# Circuito_el_trico.net
KiCad netlist of a schematic drawn in EAGLE
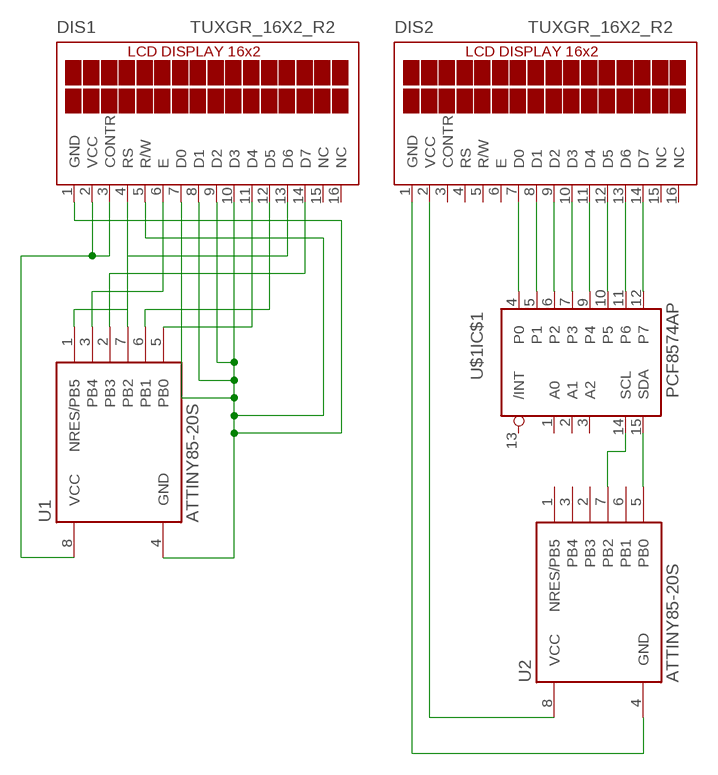
[diagram p0: schematic, sheet 1]

(export (version "E")
  (design (tool "Eeschema 10.0.6"))
  (components
    (comp (ref "DIS1")
      (value "TUXGR_16X2_R2")
      (footprint "eagle-import:TUXGR_16X2_R2")
      (libsource (lib "eagle-import") (part "TUXGR_16X2_R2"))
    )
    (comp (ref "DIS2")
      (value "TUXGR_16X2_R2")
      (footprint "eagle-import:TUXGR_16X2_R2")
      (libsource (lib "eagle-import") (part "TUXGR_16X2_R2"))
    )
    (comp (ref "U$1")
      (value "PCF8574AP")
      (footprint "eagle-import:DIL16")
      (libsource (lib "eagle-import") (part "PCF8574AP"))
    )
    (comp (ref "U1")
      (value "ATTINY85-20S")
      (footprint "eagle-import:SOIC8_EIAJ_208MIL")
      (libsource (lib "eagle-import") (part "ATTINY85S-20"))
    )
    (comp (ref "U2")
      (value "ATTINY85-20S")
      (footprint "eagle-import:SOIC8_EIAJ_208MIL")
      (libsource (lib "eagle-import") (part "ATTINY85S-20"))
    )
  )
  (nets
    (net (code "1") (name "Net-(DIS1-CONTR)") (class "Default")
      (node (ref "DIS1") (pin "2") (pinfunction "VCC_2") (pintype "power_in"))
      (node (ref "DIS1") (pin "3") (pinfunction "CONTR_3") (pintype "input"))
      (node (ref "U1") (pin "8") (pinfunction "VCC_8") (pintype "power_in"))
    )
    (net (code "2") (name "Net-(DIS1-D0)") (class "Default")
      (node (ref "DIS1") (pin "1") (pinfunction "GND_1") (pintype "power_in"))
      (node (ref "DIS1") (pin "10") (pinfunction "D3_10") (pintype "input"))
      (node (ref "DIS1") (pin "5") (pinfunction "R/W_5") (pintype "input"))
      (node (ref "DIS1") (pin "7") (pinfunction "D0_7") (pintype "input"))
      (node (ref "DIS1") (pin "8") (pinfunction "D1_8") (pintype "input"))
      (node (ref "DIS1") (pin "9") (pinfunction "D2_9") (pintype "input"))
      (node (ref "U1") (pin "4") (pinfunction "GND_4") (pintype "power_in"))
    )
    (net (code "3") (name "Net-(DIS1-D4)") (class "Default")
      (node (ref "DIS1") (pin "11") (pinfunction "D4_11") (pintype "input"))
      (node (ref "U1") (pin "5") (pinfunction "PB0_5") (pintype "bidirectional"))
    )
    (net (code "4") (name "Net-(DIS1-D5)") (class "Default")
      (node (ref "DIS1") (pin "12") (pinfunction "D5_12") (pintype "input"))
      (node (ref "U1") (pin "6") (pinfunction "PB1_6") (pintype "bidirectional"))
    )
    (net (code "5") (name "Net-(DIS1-D6)") (class "Default")
      (node (ref "DIS1") (pin "13") (pinfunction "D6_13") (pintype "input"))
      (node (ref "U1") (pin "7") (pinfunction "PB2_7") (pintype "bidirectional"))
    )
    (net (code "6") (name "Net-(DIS1-D7)") (class "Default")
      (node (ref "DIS1") (pin "14") (pinfunction "D7_14") (pintype "input"))
      (node (ref "U1") (pin "2") (pinfunction "PB3_2") (pintype "bidirectional"))
    )
    (net (code "7") (name "Net-(DIS1-E)") (class "Default")
      (node (ref "DIS1") (pin "6") (pinfunction "E_6") (pintype "input"))
      (node (ref "U1") (pin "3") (pinfunction "PB4_3") (pintype "bidirectional"))
    )
    (net (code "8") (name "Net-(DIS1-RS)") (class "Default")
      (node (ref "DIS1") (pin "4") (pinfunction "RS_4") (pintype "input"))
      (node (ref "U1") (pin "1") (pinfunction "NRES/PB5_1") (pintype "bidirectional"))
    )
    (net (code "9") (name "Net-(DIS2-D0)") (class "Default")
      (node (ref "DIS2") (pin "7") (pinfunction "D0_7") (pintype "input"))
      (node (ref "U$1") (pin "4") (pinfunction "P0_4") (pintype "bidirectional"))
    )
    (net (code "10") (name "Net-(DIS2-D1)") (class "Default")
      (node (ref "DIS2") (pin "8") (pinfunction "D1_8") (pintype "input"))
      (node (ref "U$1") (pin "5") (pinfunction "P1_5") (pintype "bidirectional"))
    )
    (net (code "11") (name "Net-(DIS2-D2)") (class "Default")
      (node (ref "DIS2") (pin "9") (pinfunction "D2_9") (pintype "input"))
      (node (ref "U$1") (pin "6") (pinfunction "P2_6") (pintype "bidirectional"))
    )
    (net (code "12") (name "Net-(DIS2-D3)") (class "Default")
      (node (ref "DIS2") (pin "10") (pinfunction "D3_10") (pintype "input"))
      (node (ref "U$1") (pin "7") (pinfunction "P3_7") (pintype "bidirectional"))
    )
    (net (code "13") (name "Net-(DIS2-D4)") (class "Default")
      (node (ref "DIS2") (pin "11") (pinfunction "D4_11") (pintype "input"))
      (node (ref "U$1") (pin "9") (pinfunction "P4_9") (pintype "bidirectional"))
    )
    (net (code "14") (name "Net-(DIS2-D5)") (class "Default")
      (node (ref "DIS2") (pin "12") (pinfunction "D5_12") (pintype "input"))
      (node (ref "U$1") (pin "10") (pinfunction "P5_10") (pintype "bidirectional"))
    )
    (net (code "15") (name "Net-(DIS2-D6)") (class "Default")
      (node (ref "DIS2") (pin "13") (pinfunction "D6_13") (pintype "input"))
      (node (ref "U$1") (pin "11") (pinfunction "P6_11") (pintype "bidirectional"))
    )
    (net (code "16") (name "Net-(DIS2-D7)") (class "Default")
      (node (ref "DIS2") (pin "14") (pinfunction "D7_14") (pintype "input"))
      (node (ref "U$1") (pin "12") (pinfunction "P7_12") (pintype "bidirectional"))
    )
    (net (code "17") (name "Net-(DIS2-GND)") (class "Default")
      (node (ref "DIS2") (pin "1") (pinfunction "GND_1") (pintype "power_in"))
      (node (ref "U2") (pin "4") (pinfunction "GND_4") (pintype "power_in"))
    )
    (net (code "18") (name "Net-(DIS2-VCC)") (class "Default")
      (node (ref "DIS2") (pin "2") (pinfunction "VCC_2") (pintype "power_in"))
      (node (ref "U2") (pin "8") (pinfunction "VCC_8") (pintype "power_in"))
    )
    (net (code "19") (name "Net-(U$1A-SCL)") (class "Default")
      (node (ref "U$1") (pin "14") (pinfunction "SCL_14") (pintype "input"))
      (node (ref "U2") (pin "7") (pinfunction "PB2_7") (pintype "bidirectional"))
    )
    (net (code "20") (name "Net-(U$1A-SDA)") (class "Default")
      (node (ref "U$1") (pin "15") (pinfunction "SDA_15") (pintype "bidirectional"))
      (node (ref "U2") (pin "5") (pinfunction "PB0_5") (pintype "bidirectional"))
    )
    (net (code "21") (name "unconnected-(DIS1-NC-Pad15)") (class "Default")
      (node (ref "DIS1") (pin "15") (pinfunction "NC_15") (pintype "no_connect"))
    )
    (net (code "22") (name "unconnected-(DIS1-NC-Pad16)") (class "Default")
      (node (ref "DIS1") (pin "16") (pinfunction "NC_16") (pintype "no_connect"))
    )
    (net (code "23") (name "unconnected-(DIS2-CONTR-Pad3)") (class "Default")
      (node (ref "DIS2") (pin "3") (pinfunction "CONTR_3") (pintype "input"))
    )
    (net (code "24") (name "unconnected-(DIS2-E-Pad6)") (class "Default")
      (node (ref "DIS2") (pin "6") (pinfunction "E_6") (pintype "input"))
    )
    (net (code "25") (name "unconnected-(DIS2-NC-Pad15)") (class "Default")
      (node (ref "DIS2") (pin "15") (pinfunction "NC_15") (pintype "no_connect"))
    )
    (net (code "26") (name "unconnected-(DIS2-NC-Pad16)") (class "Default")
      (node (ref "DIS2") (pin "16") (pinfunction "NC_16") (pintype "no_connect"))
    )
    (net (code "27") (name "unconnected-(DIS2-RS-Pad4)") (class "Default")
      (node (ref "DIS2") (pin "4") (pinfunction "RS_4") (pintype "input"))
    )
    (net (code "28") (name "unconnected-(DIS2-R{slash}W-Pad5)") (class "Default")
      (node (ref "DIS2") (pin "5") (pinfunction "R/W_5") (pintype "input"))
    )
    (net (code "29") (name "unconnected-(U$1A-A0-Pad1)") (class "Default")
      (node (ref "U$1") (pin "1") (pinfunction "A0_1") (pintype "input"))
    )
    (net (code "30") (name "unconnected-(U$1A-A1-Pad2)") (class "Default")
      (node (ref "U$1") (pin "2") (pinfunction "A1_2") (pintype "input"))
    )
    (net (code "31") (name "unconnected-(U$1A-A2-Pad3)") (class "Default")
      (node (ref "U$1") (pin "3") (pinfunction "A2_3") (pintype "input"))
    )
    (net (code "32") (name "unconnected-(U$1A-{slash}INT-Pad13)") (class "Default")
      (node (ref "U$1") (pin "13") (pinfunction "/INT_13") (pintype "output"))
    )
    (net (code "33") (name "unconnected-(U2-NRES{slash}PB5-Pad1)") (class "Default")
      (node (ref "U2") (pin "1") (pinfunction "NRES/PB5_1") (pintype "bidirectional"))
    )
    (net (code "34") (name "unconnected-(U2-PB1-Pad6)") (class "Default")
      (node (ref "U2") (pin "6") (pinfunction "PB1_6") (pintype "bidirectional"))
    )
    (net (code "35") (name "unconnected-(U2-PB3-Pad2)") (class "Default")
      (node (ref "U2") (pin "2") (pinfunction "PB3_2") (pintype "bidirectional"))
    )
    (net (code "36") (name "unconnected-(U2-PB4-Pad3)") (class "Default")
      (node (ref "U2") (pin "3") (pinfunction "PB4_3") (pintype "bidirectional"))
    )
  )
)
